# mippe_base_v2.net
KiCad netlist of a schematic drawn in EAGLE
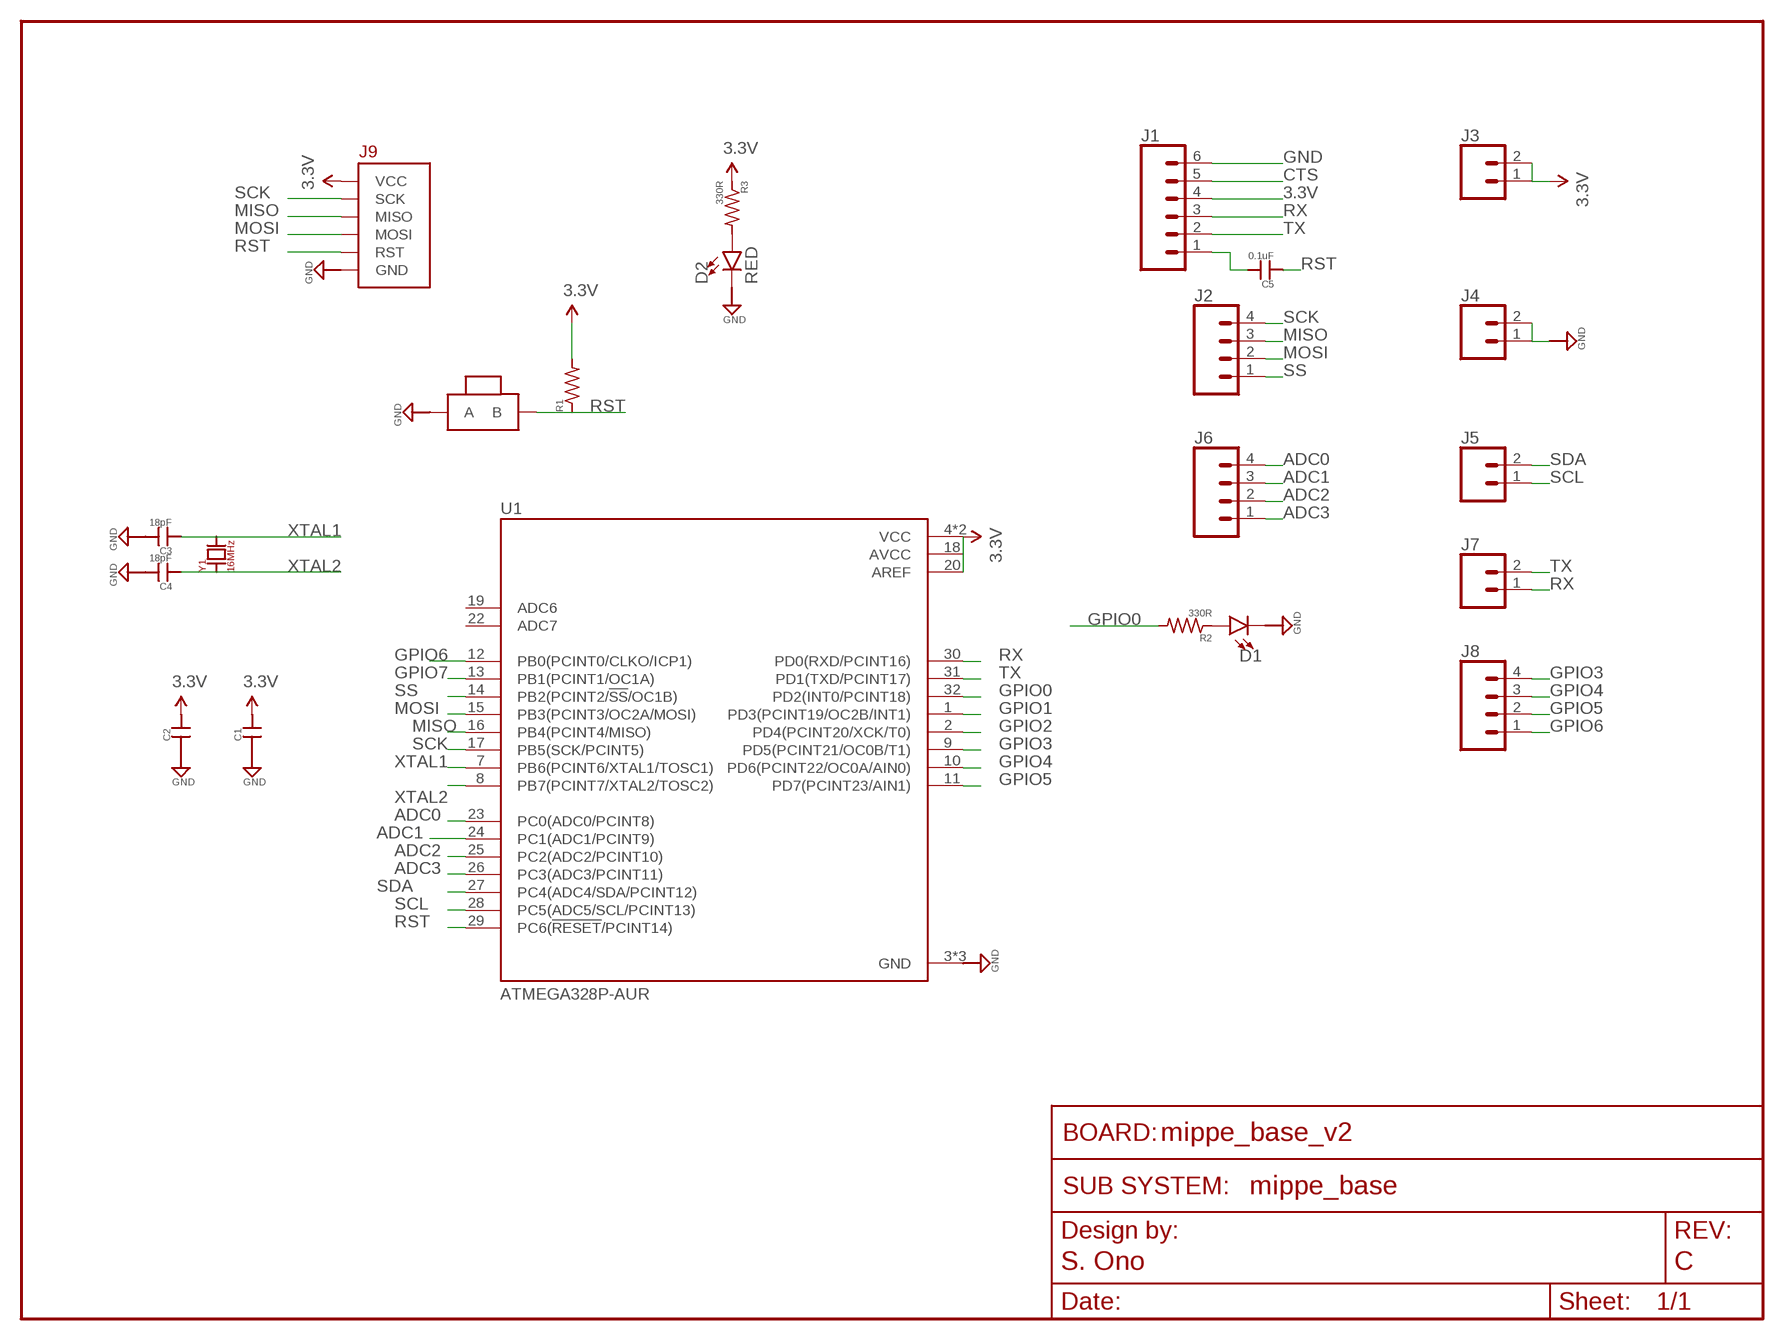
[diagram p0: schematic, sheet 1]

(export (version "E")
  (design (tool "Eeschema 10.0.6"))
  (components
    (comp (ref "C1")
      (value "CAP0603-CAP")
      (footprint "eagle-import:0603-CAP")
      (libsource (lib "eagle-import") (part "CAP0603-CAP"))
    )
    (comp (ref "C2")
      (value "CAP0603-CAP")
      (footprint "eagle-import:0603-CAP")
      (libsource (lib "eagle-import") (part "CAP0603-CAP"))
    )
    (comp (ref "C3")
      (value "18pF")
      (footprint "eagle-import:0603-CAP")
      (libsource (lib "eagle-import") (part "CAP0603-CAP"))
    )
    (comp (ref "C4")
      (value "18pF")
      (footprint "eagle-import:0603-CAP")
      (libsource (lib "eagle-import") (part "CAP0603-CAP"))
    )
    (comp (ref "C5")
      (value "0.1uF")
      (footprint "eagle-import:0603-CAP")
      (libsource (lib "eagle-import") (part "CAP0603-CAP"))
    )
    (comp (ref "D1")
      (value "LED0603")
      (footprint "eagle-import:LED-0603")
      (libsource (lib "eagle-import") (part "LED0603"))
    )
    (comp (ref "D2")
      (value "RED")
      (footprint "eagle-import:LED-0603")
      (libsource (lib "eagle-import") (part "LED0603"))
    )
    (comp (ref "J1")
      (value "CONN_06NO_SILK_FEMALE_PTH")
      (footprint "eagle-import:1X06_NO_SILK")
      (libsource (lib "eagle-import") (part "CONN_06NO_SILK_FEMALE_PTH"))
    )
    (comp (ref "J2")
      (value "CONN_041X04_NO_SILK")
      (footprint "eagle-import:1X04_NO_SILK")
      (libsource (lib "eagle-import") (part "CONN_041X04_NO_SILK"))
    )
    (comp (ref "J3")
      (value "CONN_021X02_NO_SILK")
      (footprint "eagle-import:1X02_NO_SILK")
      (libsource (lib "eagle-import") (part "CONN_021X02_NO_SILK"))
    )
    (comp (ref "J4")
      (value "CONN_021X02_NO_SILK")
      (footprint "eagle-import:1X02_NO_SILK")
      (libsource (lib "eagle-import") (part "CONN_021X02_NO_SILK"))
    )
    (comp (ref "J5")
      (value "CONN_021X02_NO_SILK")
      (footprint "eagle-import:1X02_NO_SILK")
      (libsource (lib "eagle-import") (part "CONN_021X02_NO_SILK"))
    )
    (comp (ref "J6")
      (value "CONN_041X04_NO_SILK")
      (footprint "eagle-import:1X04_NO_SILK")
      (libsource (lib "eagle-import") (part "CONN_041X04_NO_SILK"))
    )
    (comp (ref "J7")
      (value "CONN_021X02_NO_SILK")
      (footprint "eagle-import:1X02_NO_SILK")
      (libsource (lib "eagle-import") (part "CONN_021X02_NO_SILK"))
    )
    (comp (ref "J8")
      (value "CONN_041X04_NO_SILK")
      (footprint "eagle-import:1X04_NO_SILK")
      (libsource (lib "eagle-import") (part "CONN_041X04_NO_SILK"))
    )
    (comp (ref "J9")
      (value "BURNIN")
      (footprint "eagle-import:BURNIN")
      (libsource (lib "eagle-import") (part "BURNIN"))
    )
    (comp (ref "R1")
      (value "R-US_R0603")
      (footprint "eagle-import:R0603")
      (fields (field (name "MANUFACTURER") "Rohm Semiconductor"))
      (libsource (lib "eagle-import") (part "R-US_R0603"))
    )
    (comp (ref "R2")
      (value "330R")
      (footprint "eagle-import:R0603")
      (fields (field (name "MANUFACTURER") "Rohm Semiconductor"))
      (libsource (lib "eagle-import") (part "R-US_R0603"))
    )
    (comp (ref "R3")
      (value "330R")
      (footprint "eagle-import:R0603")
      (fields (field (name "MANUFACTURER") "Rohm Semiconductor"))
      (libsource (lib "eagle-import") (part "R-US_R0603"))
    )
    (comp (ref "SW1")
      (value "BTN-PTS810")
      (footprint "eagle-import:BTN_PTS810")
      (libsource (lib "eagle-import") (part "BTN-PTS810"))
    )
    (comp (ref "U1")
      (value "ATMEGA328P-AUR")
      (footprint "eagle-import:QFP80P900X900X120-32N")
      (fields (field (name "DIGI-KEY_PART_NUMBER") "ATMEGA328P-AURCT-ND") (field (name "MF") "Microchip"))
      (libsource (lib "eagle-import") (part "ATMEGA328P-AUR"))
    )
    (comp (ref "Y1")
      (value "16MHz")
      (footprint "eagle-import:XTAL500X320X130N")
      (libsource (lib "eagle-import") (part "CRYSTAL_SMOL"))
    )
  )
  (nets
    (net (code "1") (name "/ADC0") (class "Default")
      (node (ref "J6") (pin "4") (pinfunction "4_4") (pintype "passive"))
      (node (ref "U1") (pin "23") (pinfunction "PC0(ADC0/PCINT8)_23") (pintype "bidirectional"))
    )
    (net (code "2") (name "/ADC1") (class "Default")
      (node (ref "J6") (pin "3") (pinfunction "3_3") (pintype "passive"))
      (node (ref "U1") (pin "24") (pinfunction "PC1(ADC1/PCINT9)_24") (pintype "bidirectional"))
    )
    (net (code "3") (name "/ADC2") (class "Default")
      (node (ref "J6") (pin "2") (pinfunction "2_2") (pintype "passive"))
      (node (ref "U1") (pin "25") (pinfunction "PC2(ADC2/PCINT10)_25") (pintype "bidirectional"))
    )
    (net (code "4") (name "/ADC3") (class "Default")
      (node (ref "J6") (pin "1") (pinfunction "1_1") (pintype "passive"))
      (node (ref "U1") (pin "26") (pinfunction "PC3(ADC3/PCINT11)_26") (pintype "bidirectional"))
    )
    (net (code "5") (name "/CTS") (class "Default")
      (node (ref "J1") (pin "5") (pinfunction "5_5") (pintype "passive"))
    )
    (net (code "6") (name "/GPIO0") (class "Default")
      (node (ref "R2") (pin "2") (pinfunction "2_2") (pintype "passive"))
      (node (ref "U1") (pin "32") (pinfunction "PD2(INT0/PCINT18)_32") (pintype "bidirectional"))
    )
    (net (code "7") (name "/GPIO1") (class "Default")
      (node (ref "U1") (pin "1") (pinfunction "PD3(PCINT19/OC2B/INT1)_1") (pintype "bidirectional"))
    )
    (net (code "8") (name "/GPIO2") (class "Default")
      (node (ref "U1") (pin "2") (pinfunction "PD4(PCINT20/XCK/T0)_2") (pintype "bidirectional"))
    )
    (net (code "9") (name "/GPIO3") (class "Default")
      (node (ref "J8") (pin "4") (pinfunction "4_4") (pintype "passive"))
      (node (ref "U1") (pin "9") (pinfunction "PD5(PCINT21/OC0B/T1)_9") (pintype "bidirectional"))
    )
    (net (code "10") (name "/GPIO4") (class "Default")
      (node (ref "J8") (pin "3") (pinfunction "3_3") (pintype "passive"))
      (node (ref "U1") (pin "10") (pinfunction "PD6(PCINT22/OC0A/AIN0)_10") (pintype "bidirectional"))
    )
    (net (code "11") (name "/GPIO5") (class "Default")
      (node (ref "J8") (pin "2") (pinfunction "2_2") (pintype "passive"))
      (node (ref "U1") (pin "11") (pinfunction "PD7(PCINT23/AIN1)_11") (pintype "bidirectional"))
    )
    (net (code "12") (name "/GPIO6") (class "Default")
      (node (ref "J8") (pin "1") (pinfunction "1_1") (pintype "passive"))
      (node (ref "U1") (pin "12") (pinfunction "PB0(PCINT0/CLKO/ICP1)_12") (pintype "bidirectional"))
    )
    (net (code "13") (name "/GPIO7") (class "Default")
      (node (ref "U1") (pin "13") (pinfunction "PB1(PCINT1/OC1A)_13") (pintype "bidirectional"))
    )
    (net (code "14") (name "/MISO") (class "Default")
      (node (ref "J2") (pin "3") (pinfunction "3_3") (pintype "passive"))
      (node (ref "J9") (pin "MISO") (pinfunction "MISO_MISO") (pintype "bidirectional"))
      (node (ref "U1") (pin "16") (pinfunction "PB4(PCINT4/MISO)_16") (pintype "bidirectional"))
    )
    (net (code "15") (name "/MOSI") (class "Default")
      (node (ref "J2") (pin "2") (pinfunction "2_2") (pintype "passive"))
      (node (ref "J9") (pin "MOSI") (pinfunction "MOSI_MOSI") (pintype "bidirectional"))
      (node (ref "U1") (pin "15") (pinfunction "PB3(PCINT3/OC2A/MOSI)_15") (pintype "bidirectional"))
    )
    (net (code "16") (name "/RST") (class "Default")
      (node (ref "C5") (pin "1") (pinfunction "1_1") (pintype "passive"))
      (node (ref "J9") (pin "RST") (pinfunction "RST_RST") (pintype "bidirectional"))
      (node (ref "R1") (pin "1") (pinfunction "1_1") (pintype "passive"))
      (node (ref "SW1") (pin "3") (pinfunction "B_3") (pintype "bidirectional"))
      (node (ref "SW1") (pin "4") (pinfunction "B_4") (pintype "bidirectional"))
      (node (ref "U1") (pin "29") (pinfunction "PC6(~{RESET}/PCINT14)_29") (pintype "bidirectional"))
    )
    (net (code "17") (name "/RX") (class "Default")
      (node (ref "J1") (pin "3") (pinfunction "3_3") (pintype "passive"))
      (node (ref "J7") (pin "1") (pinfunction "1_1") (pintype "passive"))
      (node (ref "U1") (pin "30") (pinfunction "PD0(RXD/PCINT16)_30") (pintype "bidirectional"))
    )
    (net (code "18") (name "/SCK") (class "Default")
      (node (ref "J2") (pin "4") (pinfunction "4_4") (pintype "passive"))
      (node (ref "J9") (pin "SCK") (pinfunction "SCK_SCK") (pintype "bidirectional"))
      (node (ref "U1") (pin "17") (pinfunction "PB5(SCK/PCINT5)_17") (pintype "bidirectional"))
    )
    (net (code "19") (name "/SCL") (class "Default")
      (node (ref "J5") (pin "1") (pinfunction "1_1") (pintype "passive"))
      (node (ref "U1") (pin "28") (pinfunction "PC5(ADC5/SCL/PCINT13)_28") (pintype "bidirectional"))
    )
    (net (code "20") (name "/SDA") (class "Default")
      (node (ref "J5") (pin "2") (pinfunction "2_2") (pintype "passive"))
      (node (ref "U1") (pin "27") (pinfunction "PC4(ADC4/SDA/PCINT12)_27") (pintype "bidirectional"))
    )
    (net (code "21") (name "/SS") (class "Default")
      (node (ref "J2") (pin "1") (pinfunction "1_1") (pintype "passive"))
      (node (ref "U1") (pin "14") (pinfunction "PB2(PCINT2/~{SS}/OC1B)_14") (pintype "bidirectional"))
    )
    (net (code "22") (name "/TX") (class "Default")
      (node (ref "J1") (pin "2") (pinfunction "2_2") (pintype "passive"))
      (node (ref "J7") (pin "2") (pinfunction "2_2") (pintype "passive"))
      (node (ref "U1") (pin "31") (pinfunction "PD1(TXD/PCINT17)_31") (pintype "bidirectional"))
    )
    (net (code "23") (name "/XTAL1") (class "Default")
      (node (ref "C3") (pin "1") (pinfunction "1_1") (pintype "passive"))
      (node (ref "U1") (pin "7") (pinfunction "PB6(PCINT6/XTAL1/TOSC1)_7") (pintype "bidirectional"))
      (node (ref "Y1") (pin "2") (pinfunction "B_2") (pintype "passive"))
    )
    (net (code "24") (name "/XTAL2") (class "Default")
      (node (ref "C4") (pin "1") (pinfunction "1_1") (pintype "passive"))
      (node (ref "U1") (pin "8") (pinfunction "PB7(PCINT7/XTAL2/TOSC2)_8") (pintype "bidirectional"))
      (node (ref "Y1") (pin "1") (pinfunction "A_1") (pintype "passive"))
    )
    (net (code "25") (name "3.3V") (class "Default")
      (node (ref "C1") (pin "2") (pinfunction "2_2") (pintype "passive"))
      (node (ref "C2") (pin "2") (pinfunction "2_2") (pintype "passive"))
      (node (ref "J1") (pin "4") (pinfunction "4_4") (pintype "passive"))
      (node (ref "J3") (pin "1") (pinfunction "1_1") (pintype "passive"))
      (node (ref "J3") (pin "2") (pinfunction "2_2") (pintype "passive"))
      (node (ref "J9") (pin "3.3V") (pinfunction "VCC_3.3V") (pintype "power_in"))
      (node (ref "R1") (pin "2") (pinfunction "2_2") (pintype "passive"))
      (node (ref "R3") (pin "1") (pinfunction "1_1") (pintype "passive"))
      (node (ref "U1") (pin "18") (pinfunction "AVCC_18") (pintype "power_in"))
      (node (ref "U1") (pin "20") (pinfunction "AREF_20") (pintype "power_in"))
      (node (ref "U1") (pin "4") (pinfunction "VCC_4") (pintype "power_in"))
      (node (ref "U1") (pin "6") (pinfunction "VCC_6") (pintype "power_in"))
    )
    (net (code "26") (name "GND") (class "Default")
      (node (ref "C1") (pin "1") (pinfunction "1_1") (pintype "passive"))
      (node (ref "C2") (pin "1") (pinfunction "1_1") (pintype "passive"))
      (node (ref "C3") (pin "2") (pinfunction "2_2") (pintype "passive"))
      (node (ref "C4") (pin "2") (pinfunction "2_2") (pintype "passive"))
      (node (ref "D1") (pin "C") (pinfunction "C_C") (pintype "passive"))
      (node (ref "D2") (pin "C") (pinfunction "C_C") (pintype "passive"))
      (node (ref "J1") (pin "6") (pinfunction "6_6") (pintype "passive"))
      (node (ref "J4") (pin "1") (pinfunction "1_1") (pintype "passive"))
      (node (ref "J4") (pin "2") (pinfunction "2_2") (pintype "passive"))
      (node (ref "J9") (pin "GND") (pinfunction "GND_GND") (pintype "power_in"))
      (node (ref "SW1") (pin "1") (pinfunction "A_1") (pintype "bidirectional"))
      (node (ref "SW1") (pin "2") (pinfunction "A_2") (pintype "bidirectional"))
      (node (ref "U1") (pin "21") (pinfunction "GND_21") (pintype "power_in"))
      (node (ref "U1") (pin "3") (pinfunction "GND_3") (pintype "power_in"))
      (node (ref "U1") (pin "5") (pinfunction "GND_5") (pintype "power_in"))
    )
    (net (code "27") (name "Net-(C5-Pad2)") (class "Default")
      (node (ref "C5") (pin "2") (pinfunction "2_2") (pintype "passive"))
      (node (ref "J1") (pin "1") (pinfunction "1_1") (pintype "passive"))
    )
    (net (code "28") (name "Net-(D1-PadA)") (class "Default")
      (node (ref "D1") (pin "A") (pinfunction "A_A") (pintype "passive"))
      (node (ref "R2") (pin "1") (pinfunction "1_1") (pintype "passive"))
    )
    (net (code "29") (name "Net-(D2-PadA)") (class "Default")
      (node (ref "D2") (pin "A") (pinfunction "A_A") (pintype "passive"))
      (node (ref "R3") (pin "2") (pinfunction "2_2") (pintype "passive"))
    )
    (net (code "30") (name "unconnected-(U1-ADC6-Pad19)") (class "Default")
      (node (ref "U1") (pin "19") (pinfunction "ADC6_19") (pintype "input"))
    )
    (net (code "31") (name "unconnected-(U1-ADC7-Pad22)") (class "Default")
      (node (ref "U1") (pin "22") (pinfunction "ADC7_22") (pintype "input"))
    )
  )
)
